# eBox_ACdetect.net
KiCad netlist of a schematic drawn in Altium Designer
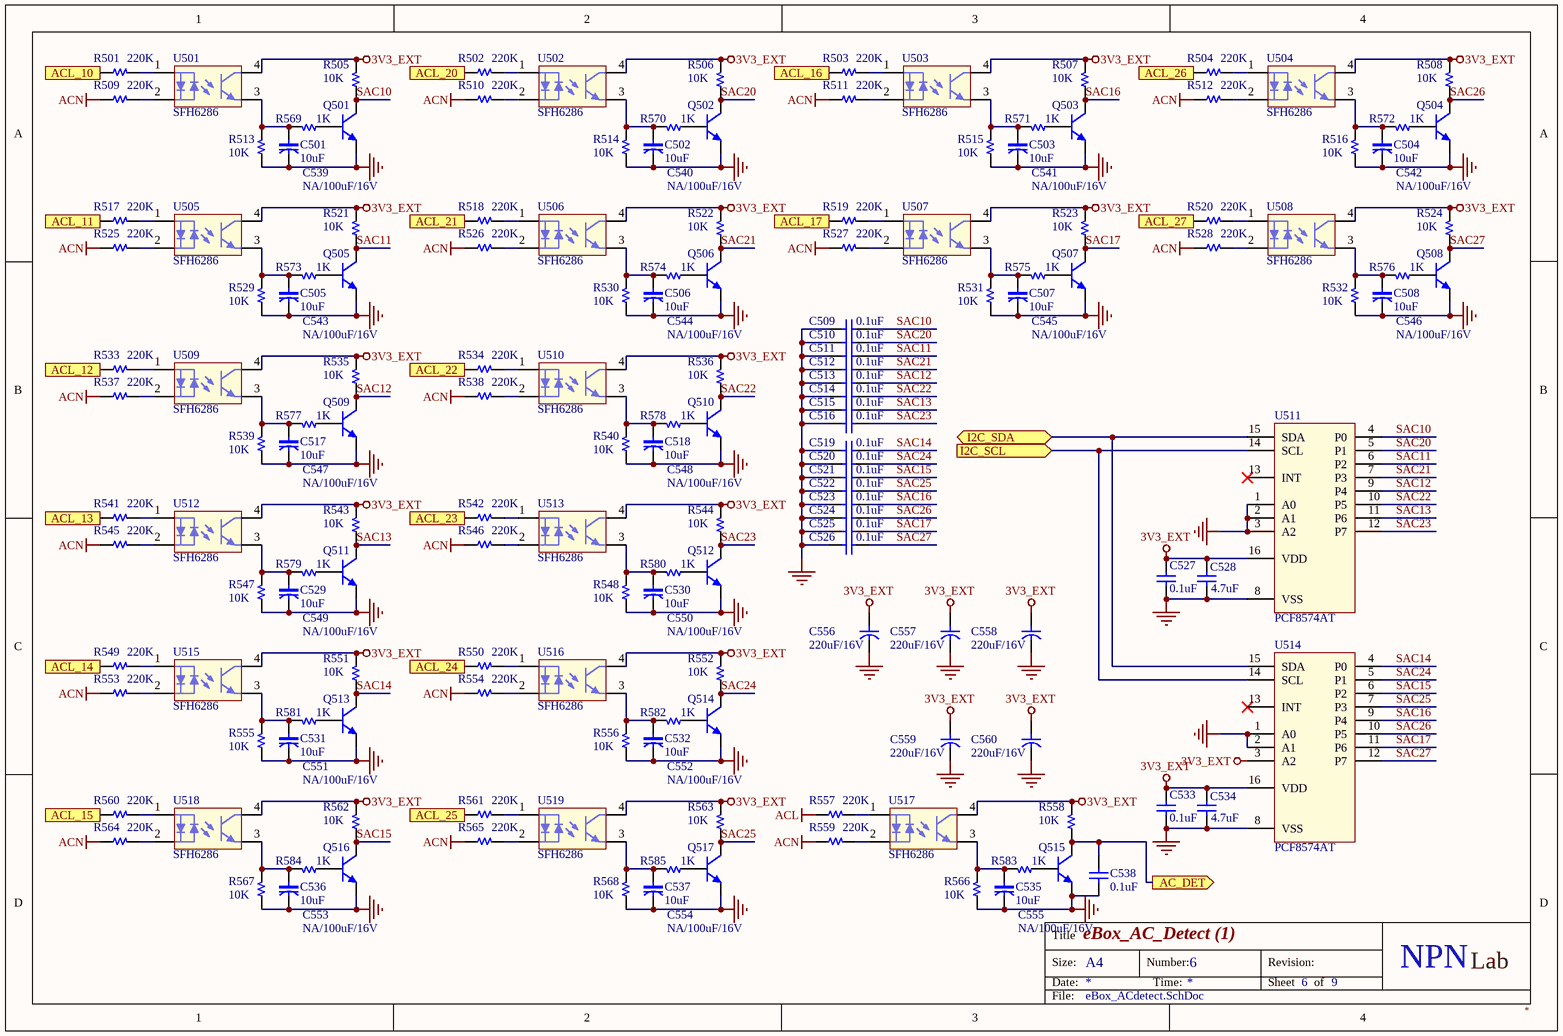
[diagram p0: eBox_ACdetect.SchDoc]

(export (version "E")
  (design (tool "Eeschema 10.0.6"))
  (components
    (comp (ref "C501")
      (value "10uF")
      (footprint "C 0805")
      (description "CAP CER 0.1UF 50V X7R 0805")
      (libsource (lib "chipfc_altium_libs") (part "Capacitor NP"))
    )
    (comp (ref "C502")
      (value "10uF")
      (footprint "C 0805")
      (description "CAP CER 0.1UF 50V X7R 0805")
      (libsource (lib "chipfc_altium_libs") (part "Capacitor NP"))
    )
    (comp (ref "C503")
      (value "10uF")
      (footprint "C 0805")
      (description "CAP CER 0.1UF 50V X7R 0805")
      (libsource (lib "chipfc_altium_libs") (part "Capacitor NP"))
    )
    (comp (ref "C504")
      (value "10uF")
      (footprint "C 0805")
      (description "CAP CER 0.1UF 50V X7R 0805")
      (libsource (lib "chipfc_altium_libs") (part "Capacitor NP"))
    )
    (comp (ref "C505")
      (value "10uF")
      (footprint "C 0805")
      (description "CAP CER 0.1UF 50V X7R 0805")
      (libsource (lib "chipfc_altium_libs") (part "Capacitor NP"))
    )
    (comp (ref "C506")
      (value "10uF")
      (footprint "C 0805")
      (description "CAP CER 0.1UF 50V X7R 0805")
      (libsource (lib "chipfc_altium_libs") (part "Capacitor NP"))
    )
    (comp (ref "C507")
      (value "10uF")
      (footprint "C 0805")
      (description "CAP CER 0.1UF 50V X7R 0805")
      (libsource (lib "chipfc_altium_libs") (part "Capacitor NP"))
    )
    (comp (ref "C508")
      (value "10uF")
      (footprint "C 0805")
      (description "CAP CER 0.1UF 50V X7R 0805")
      (libsource (lib "chipfc_altium_libs") (part "Capacitor NP"))
    )
    (comp (ref "C509")
      (value "0.1uF")
      (footprint "C 0805")
      (description "CAP CER 0.1UF 50V X7R 0805")
      (libsource (lib "chipfc_altium_libs") (part "Capacitor NP"))
    )
    (comp (ref "C510")
      (value "0.1uF")
      (footprint "C 0805")
      (description "CAP CER 0.1UF 50V X7R 0805")
      (libsource (lib "chipfc_altium_libs") (part "Capacitor NP"))
    )
    (comp (ref "C511")
      (value "0.1uF")
      (footprint "C 0805")
      (description "CAP CER 0.1UF 50V X7R 0805")
      (libsource (lib "chipfc_altium_libs") (part "Capacitor NP"))
    )
    (comp (ref "C512")
      (value "0.1uF")
      (footprint "C 0805")
      (description "CAP CER 0.1UF 50V X7R 0805")
      (libsource (lib "chipfc_altium_libs") (part "Capacitor NP"))
    )
    (comp (ref "C513")
      (value "0.1uF")
      (footprint "C 0805")
      (description "CAP CER 0.1UF 50V X7R 0805")
      (libsource (lib "chipfc_altium_libs") (part "Capacitor NP"))
    )
    (comp (ref "C514")
      (value "0.1uF")
      (footprint "C 0805")
      (description "CAP CER 0.1UF 50V X7R 0805")
      (libsource (lib "chipfc_altium_libs") (part "Capacitor NP"))
    )
    (comp (ref "C515")
      (value "0.1uF")
      (footprint "C 0805")
      (description "CAP CER 0.1UF 50V X7R 0805")
      (libsource (lib "chipfc_altium_libs") (part "Capacitor NP"))
    )
    (comp (ref "C516")
      (value "0.1uF")
      (footprint "C 0805")
      (description "CAP CER 0.1UF 50V X7R 0805")
      (libsource (lib "chipfc_altium_libs") (part "Capacitor NP"))
    )
    (comp (ref "C517")
      (value "10uF")
      (footprint "C 0805")
      (description "CAP CER 0.1UF 50V X7R 0805")
      (libsource (lib "chipfc_altium_libs") (part "Capacitor NP"))
    )
    (comp (ref "C518")
      (value "10uF")
      (footprint "C 0805")
      (description "CAP CER 0.1UF 50V X7R 0805")
      (libsource (lib "chipfc_altium_libs") (part "Capacitor NP"))
    )
    (comp (ref "C519")
      (value "0.1uF")
      (footprint "C 0805")
      (description "CAP CER 0.1UF 50V X7R 0805")
      (libsource (lib "chipfc_altium_libs") (part "Capacitor NP"))
    )
    (comp (ref "C520")
      (value "0.1uF")
      (footprint "C 0805")
      (description "CAP CER 0.1UF 50V X7R 0805")
      (libsource (lib "chipfc_altium_libs") (part "Capacitor NP"))
    )
    (comp (ref "C521")
      (value "0.1uF")
      (footprint "C 0805")
      (description "CAP CER 0.1UF 50V X7R 0805")
      (libsource (lib "chipfc_altium_libs") (part "Capacitor NP"))
    )
    (comp (ref "C522")
      (value "0.1uF")
      (footprint "C 0805")
      (description "CAP CER 0.1UF 50V X7R 0805")
      (libsource (lib "chipfc_altium_libs") (part "Capacitor NP"))
    )
    (comp (ref "C523")
      (value "0.1uF")
      (footprint "C 0805")
      (description "CAP CER 0.1UF 50V X7R 0805")
      (libsource (lib "chipfc_altium_libs") (part "Capacitor NP"))
    )
    (comp (ref "C524")
      (value "0.1uF")
      (footprint "C 0805")
      (description "CAP CER 0.1UF 50V X7R 0805")
      (libsource (lib "chipfc_altium_libs") (part "Capacitor NP"))
    )
    (comp (ref "C525")
      (value "0.1uF")
      (footprint "C 0805")
      (description "CAP CER 0.1UF 50V X7R 0805")
      (libsource (lib "chipfc_altium_libs") (part "Capacitor NP"))
    )
    (comp (ref "C526")
      (value "0.1uF")
      (footprint "C 0805")
      (description "CAP CER 0.1UF 50V X7R 0805")
      (libsource (lib "chipfc_altium_libs") (part "Capacitor NP"))
    )
    (comp (ref "C527")
      (value "0.1uF")
      (footprint "C 0603")
      (description "CAP CER 0.1UF 50V X7R 0603")
      (libsource (lib "chipfc_altium_libs") (part "Capacitor NP"))
    )
    (comp (ref "C528")
      (value "4.7uF")
      (footprint "C 0603")
      (description "CAP CER 4.7UF 50V X7R 0603")
      (libsource (lib "chipfc_altium_libs") (part "Capacitor NP"))
    )
    (comp (ref "C529")
      (value "10uF")
      (footprint "C 0805")
      (description "CAP CER 0.1UF 50V X7R 0805")
      (libsource (lib "chipfc_altium_libs") (part "Capacitor NP"))
    )
    (comp (ref "C530")
      (value "10uF")
      (footprint "C 0805")
      (description "CAP CER 0.1UF 50V X7R 0805")
      (libsource (lib "chipfc_altium_libs") (part "Capacitor NP"))
    )
    (comp (ref "C531")
      (value "10uF")
      (footprint "C 0805")
      (description "CAP CER 0.1UF 50V X7R 0805")
      (libsource (lib "chipfc_altium_libs") (part "Capacitor NP"))
    )
    (comp (ref "C532")
      (value "10uF")
      (footprint "C 0805")
      (description "CAP CER 0.1UF 50V X7R 0805")
      (libsource (lib "chipfc_altium_libs") (part "Capacitor NP"))
    )
    (comp (ref "C533")
      (value "0.1uF")
      (footprint "C 0603")
      (description "CAP CER 0.1UF 50V X7R 0603")
      (libsource (lib "chipfc_altium_libs") (part "Capacitor NP"))
    )
    (comp (ref "C534")
      (value "4.7uF")
      (footprint "C 0603")
      (description "CAP CER 4.7UF 50V X7R 0603")
      (libsource (lib "chipfc_altium_libs") (part "Capacitor NP"))
    )
    (comp (ref "C535")
      (value "10uF")
      (footprint "C 0805")
      (description "CAP CER 0.1UF 50V X7R 0805")
      (libsource (lib "chipfc_altium_libs") (part "Capacitor NP"))
    )
    (comp (ref "C536")
      (value "10uF")
      (footprint "C 0805")
      (description "CAP CER 0.1UF 50V X7R 0805")
      (libsource (lib "chipfc_altium_libs") (part "Capacitor NP"))
    )
    (comp (ref "C537")
      (value "10uF")
      (footprint "C 0805")
      (description "CAP CER 0.1UF 50V X7R 0805")
      (libsource (lib "chipfc_altium_libs") (part "Capacitor NP"))
    )
    (comp (ref "C538")
      (value "0.1uF")
      (footprint "C 0805")
      (description "CAP CER 0.1UF 50V X7R 0805")
      (libsource (lib "chipfc_altium_libs") (part "Capacitor NP"))
    )
    (comp (ref "C539")
      (value "NA/100uF/16V")
      (footprint "CYL/D.200/LS.75")
      (description "CAP ALUM 100UF 20% 16V RADIAL")
      (libsource (lib "chipfc_altium_libs") (part "Capacitor"))
    )
    (comp (ref "C540")
      (value "NA/100uF/16V")
      (footprint "CYL/D.200/LS.75")
      (description "CAP ALUM 100UF 20% 16V RADIAL")
      (libsource (lib "chipfc_altium_libs") (part "Capacitor"))
    )
    (comp (ref "C541")
      (value "NA/100uF/16V")
      (footprint "CYL/D.200/LS.75")
      (description "CAP ALUM 100UF 20% 16V RADIAL")
      (libsource (lib "chipfc_altium_libs") (part "Capacitor"))
    )
    (comp (ref "C542")
      (value "NA/100uF/16V")
      (footprint "CYL/D.200/LS.75")
      (description "CAP ALUM 100UF 20% 16V RADIAL")
      (libsource (lib "chipfc_altium_libs") (part "Capacitor"))
    )
    (comp (ref "C543")
      (value "NA/100uF/16V")
      (footprint "CYL/D.200/LS.75")
      (description "CAP ALUM 100UF 20% 16V RADIAL")
      (libsource (lib "chipfc_altium_libs") (part "Capacitor"))
    )
    (comp (ref "C544")
      (value "NA/100uF/16V")
      (footprint "CYL/D.200/LS.75")
      (description "CAP ALUM 100UF 20% 16V RADIAL")
      (libsource (lib "chipfc_altium_libs") (part "Capacitor"))
    )
    (comp (ref "C545")
      (value "NA/100uF/16V")
      (footprint "CYL/D.200/LS.75")
      (description "CAP ALUM 100UF 20% 16V RADIAL")
      (libsource (lib "chipfc_altium_libs") (part "Capacitor"))
    )
    (comp (ref "C546")
      (value "NA/100uF/16V")
      (footprint "CYL/D.200/LS.75")
      (description "CAP ALUM 100UF 20% 16V RADIAL")
      (libsource (lib "chipfc_altium_libs") (part "Capacitor"))
    )
    (comp (ref "C547")
      (value "NA/100uF/16V")
      (footprint "CYL/D.200/LS.75")
      (description "CAP ALUM 100UF 20% 16V RADIAL")
      (libsource (lib "chipfc_altium_libs") (part "Capacitor"))
    )
    (comp (ref "C548")
      (value "NA/100uF/16V")
      (footprint "CYL/D.200/LS.75")
      (description "CAP ALUM 100UF 20% 16V RADIAL")
      (libsource (lib "chipfc_altium_libs") (part "Capacitor"))
    )
    (comp (ref "C549")
      (value "NA/100uF/16V")
      (footprint "CYL/D.200/LS.75")
      (description "CAP ALUM 100UF 20% 16V RADIAL")
      (libsource (lib "chipfc_altium_libs") (part "Capacitor"))
    )
    (comp (ref "C550")
      (value "NA/100uF/16V")
      (footprint "CYL/D.200/LS.75")
      (description "CAP ALUM 100UF 20% 16V RADIAL")
      (libsource (lib "chipfc_altium_libs") (part "Capacitor"))
    )
    (comp (ref "C551")
      (value "NA/100uF/16V")
      (footprint "CYL/D.200/LS.75")
      (description "CAP ALUM 100UF 20% 16V RADIAL")
      (libsource (lib "chipfc_altium_libs") (part "Capacitor"))
    )
    (comp (ref "C552")
      (value "NA/100uF/16V")
      (footprint "CYL/D.200/LS.75")
      (description "CAP ALUM 100UF 20% 16V RADIAL")
      (libsource (lib "chipfc_altium_libs") (part "Capacitor"))
    )
    (comp (ref "C553")
      (value "NA/100uF/16V")
      (footprint "CYL/D.200/LS.75")
      (description "CAP ALUM 100UF 20% 16V RADIAL")
      (libsource (lib "chipfc_altium_libs") (part "Capacitor"))
    )
    (comp (ref "C554")
      (value "NA/100uF/16V")
      (footprint "CYL/D.200/LS.75")
      (description "CAP ALUM 100UF 20% 16V RADIAL")
      (libsource (lib "chipfc_altium_libs") (part "Capacitor"))
    )
    (comp (ref "C555")
      (value "NA/100uF/16V")
      (footprint "CYL/D.200/LS.75")
      (description "CAP ALUM 100UF 20% 16V RADIAL")
      (libsource (lib "chipfc_altium_libs") (part "Capacitor"))
    )
    (comp (ref "C556")
      (value "220uF/16V")
      (footprint "CYL/D.250/LS.100")
      (description "CAP ALUM 220UF 20% 16V RADIAL")
      (libsource (lib "") (part "Capacitor_1"))
    )
    (comp (ref "C557")
      (value "220uF/16V")
      (footprint "CYL/D.250/LS.100")
      (description "CAP ALUM 220UF 20% 16V RADIAL")
      (libsource (lib "") (part "Capacitor_1"))
    )
    (comp (ref "C558")
      (value "220uF/16V")
      (footprint "CYL/D.250/LS.100")
      (description "CAP ALUM 220UF 20% 16V RADIAL")
      (libsource (lib "") (part "Capacitor_1"))
    )
    (comp (ref "C559")
      (value "220uF/16V")
      (footprint "CYL/D.250/LS.100")
      (description "CAP ALUM 220UF 20% 16V RADIAL")
      (libsource (lib "") (part "Capacitor_1"))
    )
    (comp (ref "C560")
      (value "220uF/16V")
      (footprint "CYL/D.250/LS.100")
      (description "CAP ALUM 220UF 20% 16V RADIAL")
      (libsource (lib "") (part "Capacitor_1"))
    )
    (comp (ref "Q501")
      (value "MMBT3904LT1G")
      (footprint "SOT-23")
      (description "TRANS NPN 40V 0.2A SOT23")
      (libsource (lib "chipfc_altium_libs") (part "Transistor NPN"))
    )
    (comp (ref "Q502")
      (value "MMBT3904LT1G")
      (footprint "SOT-23")
      (description "TRANS NPN 40V 0.2A SOT23")
      (libsource (lib "chipfc_altium_libs") (part "Transistor NPN"))
    )
    (comp (ref "Q503")
      (value "MMBT3904LT1G")
      (footprint "SOT-23")
      (description "TRANS NPN 40V 0.2A SOT23")
      (libsource (lib "chipfc_altium_libs") (part "Transistor NPN"))
    )
    (comp (ref "Q504")
      (value "MMBT3904LT1G")
      (footprint "SOT-23")
      (description "TRANS NPN 40V 0.2A SOT23")
      (libsource (lib "chipfc_altium_libs") (part "Transistor NPN"))
    )
    (comp (ref "Q505")
      (value "MMBT3904LT1G")
      (footprint "SOT-23")
      (description "TRANS NPN 40V 0.2A SOT23")
      (libsource (lib "chipfc_altium_libs") (part "Transistor NPN"))
    )
    (comp (ref "Q506")
      (value "MMBT3904LT1G")
      (footprint "SOT-23")
      (description "TRANS NPN 40V 0.2A SOT23")
      (libsource (lib "chipfc_altium_libs") (part "Transistor NPN"))
    )
    (comp (ref "Q507")
      (value "MMBT3904LT1G")
      (footprint "SOT-23")
      (description "TRANS NPN 40V 0.2A SOT23")
      (libsource (lib "chipfc_altium_libs") (part "Transistor NPN"))
    )
    (comp (ref "Q508")
      (value "MMBT3904LT1G")
      (footprint "SOT-23")
      (description "TRANS NPN 40V 0.2A SOT23")
      (libsource (lib "chipfc_altium_libs") (part "Transistor NPN"))
    )
    (comp (ref "Q509")
      (value "MMBT3904LT1G")
      (footprint "SOT-23")
      (description "TRANS NPN 40V 0.2A SOT23")
      (libsource (lib "chipfc_altium_libs") (part "Transistor NPN"))
    )
    (comp (ref "Q510")
      (value "MMBT3904LT1G")
      (footprint "SOT-23")
      (description "TRANS NPN 40V 0.2A SOT23")
      (libsource (lib "chipfc_altium_libs") (part "Transistor NPN"))
    )
    (comp (ref "Q511")
      (value "MMBT3904LT1G")
      (footprint "SOT-23")
      (description "TRANS NPN 40V 0.2A SOT23")
      (libsource (lib "chipfc_altium_libs") (part "Transistor NPN"))
    )
    (comp (ref "Q512")
      (value "MMBT3904LT1G")
      (footprint "SOT-23")
      (description "TRANS NPN 40V 0.2A SOT23")
      (libsource (lib "chipfc_altium_libs") (part "Transistor NPN"))
    )
    (comp (ref "Q513")
      (value "MMBT3904LT1G")
      (footprint "SOT-23")
      (description "TRANS NPN 40V 0.2A SOT23")
      (libsource (lib "chipfc_altium_libs") (part "Transistor NPN"))
    )
    (comp (ref "Q514")
      (value "MMBT3904LT1G")
      (footprint "SOT-23")
      (description "TRANS NPN 40V 0.2A SOT23")
      (libsource (lib "chipfc_altium_libs") (part "Transistor NPN"))
    )
    (comp (ref "Q515")
      (value "MMBT3904LT1G")
      (footprint "SOT-23")
      (description "TRANS NPN 40V 0.2A SOT23")
      (libsource (lib "chipfc_altium_libs") (part "Transistor NPN"))
    )
    (comp (ref "Q516")
      (value "MMBT3904LT1G")
      (footprint "SOT-23")
      (description "TRANS NPN 40V 0.2A SOT23")
      (libsource (lib "chipfc_altium_libs") (part "Transistor NPN"))
    )
    (comp (ref "Q517")
      (value "MMBT3904LT1G")
      (footprint "SOT-23")
      (description "TRANS NPN 40V 0.2A SOT23")
      (libsource (lib "chipfc_altium_libs") (part "Transistor NPN"))
    )
    (comp (ref "R501")
      (value "220K")
      (footprint "R 0805")
      (description "RES SMD 220K OHM 1% 1/8W 0805")
      (libsource (lib "chipfc_altium_libs") (part "Resistor"))
    )
    (comp (ref "R502")
      (value "220K")
      (footprint "R 0805")
      (description "RES SMD 220K OHM 1% 1/8W 0805")
      (libsource (lib "chipfc_altium_libs") (part "Resistor"))
    )
    (comp (ref "R503")
      (value "220K")
      (footprint "R 0805")
      (description "RES SMD 220K OHM 1% 1/8W 0805")
      (libsource (lib "chipfc_altium_libs") (part "Resistor"))
    )
    (comp (ref "R504")
      (value "220K")
      (footprint "R 0805")
      (description "RES SMD 220K OHM 1% 1/8W 0805")
      (libsource (lib "chipfc_altium_libs") (part "Resistor"))
    )
    (comp (ref "R505")
      (value "10K")
      (footprint "R 0805")
      (description "RES SMD 10K OHM 1% 1/8W 0805")
      (libsource (lib "chipfc_altium_libs") (part "Resistor"))
    )
    (comp (ref "R506")
      (value "10K")
      (footprint "R 0805")
      (description "RES SMD 10K OHM 1% 1/8W 0805")
      (libsource (lib "chipfc_altium_libs") (part "Resistor"))
    )
    (comp (ref "R507")
      (value "10K")
      (footprint "R 0805")
      (description "RES SMD 10K OHM 1% 1/8W 0805")
      (libsource (lib "chipfc_altium_libs") (part "Resistor"))
    )
    (comp (ref "R508")
      (value "10K")
      (footprint "R 0805")
      (description "RES SMD 10K OHM 1% 1/8W 0805")
      (libsource (lib "chipfc_altium_libs") (part "Resistor"))
    )
    (comp (ref "R509")
      (value "220K")
      (footprint "R 0805")
      (description "RES SMD 220K OHM 1% 1/8W 0805")
      (libsource (lib "chipfc_altium_libs") (part "Resistor"))
    )
    (comp (ref "R510")
      (value "220K")
      (footprint "R 0805")
      (description "RES SMD 220K OHM 1% 1/8W 0805")
      (libsource (lib "chipfc_altium_libs") (part "Resistor"))
    )
    (comp (ref "R511")
      (value "220K")
      (footprint "R 0805")
      (description "RES SMD 220K OHM 1% 1/8W 0805")
      (libsource (lib "chipfc_altium_libs") (part "Resistor"))
    )
    (comp (ref "R512")
      (value "220K")
      (footprint "R 0805")
      (description "RES SMD 220K OHM 1% 1/8W 0805")
      (libsource (lib "chipfc_altium_libs") (part "Resistor"))
    )
    (comp (ref "R513")
      (value "10K")
      (footprint "R 0805")
      (description "RES SMD 10K OHM 1% 1/8W 0805")
      (libsource (lib "chipfc_altium_libs") (part "Resistor"))
    )
    (comp (ref "R514")
      (value "10K")
      (footprint "R 0805")
      (description "RES SMD 10K OHM 1% 1/8W 0805")
      (libsource (lib "chipfc_altium_libs") (part "Resistor"))
    )
    (comp (ref "R515")
      (value "10K")
      (footprint "R 0805")
      (description "RES SMD 10K OHM 1% 1/8W 0805")
      (libsource (lib "chipfc_altium_libs") (part "Resistor"))
    )
    (comp (ref "R516")
      (value "10K")
      (footprint "R 0805")
      (description "RES SMD 10K OHM 1% 1/8W 0805")
      (libsource (lib "chipfc_altium_libs") (part "Resistor"))
    )
    (comp (ref "R517")
      (value "220K")
      (footprint "R 0805")
      (description "RES SMD 220K OHM 1% 1/8W 0805")
      (libsource (lib "chipfc_altium_libs") (part "Resistor"))
    )
    (comp (ref "R518")
      (value "220K")
      (footprint "R 0805")
      (description "RES SMD 220K OHM 1% 1/8W 0805")
      (libsource (lib "chipfc_altium_libs") (part "Resistor"))
    )
    (comp (ref "R519")
      (value "220K")
      (footprint "R 0805")
      (description "RES SMD 220K OHM 1% 1/8W 0805")
      (libsource (lib "chipfc_altium_libs") (part "Resistor"))
    )
    (comp (ref "R520")
      (value "220K")
      (footprint "R 0805")
      (description "RES SMD 220K OHM 1% 1/8W 0805")
      (libsource (lib "chipfc_altium_libs") (part "Resistor"))
    )
    (comp (ref "R521")
      (value "10K")
      (footprint "R 0805")
      (description "RES SMD 10K OHM 1% 1/8W 0805")
      (libsource (lib "chipfc_altium_libs") (part "Resistor"))
    )
    (comp (ref "R522")
      (value "10K")
      (footprint "R 0805")
      (description "RES SMD 10K OHM 1% 1/8W 0805")
      (libsource (lib "chipfc_altium_libs") (part "Resistor"))
    )
    (comp (ref "R523")
      (value "10K")
      (footprint "R 0805")
      (description "RES SMD 10K OHM 1% 1/8W 0805")
      (libsource (lib "chipfc_altium_libs") (part "Resistor"))
    )
    (comp (ref "R524")
      (value "10K")
      (footprint "R 0805")
      (description "RES SMD 10K OHM 1% 1/8W 0805")
      (libsource (lib "chipfc_altium_libs") (part "Resistor"))
    )
    (comp (ref "R525")
      (value "220K")
      (footprint "R 0805")
      (description "RES SMD 220K OHM 1% 1/8W 0805")
      (libsource (lib "chipfc_altium_libs") (part "Resistor"))
    )
    (comp (ref "R526")
      (value "220K")
      (footprint "R 0805")
      (description "RES SMD 220K OHM 1% 1/8W 0805")
      (libsource (lib "chipfc_altium_libs") (part "Resistor"))
    )
    (comp (ref "R527")
      (value "220K")
      (footprint "R 0805")
      (description "RES SMD 220K OHM 1% 1/8W 0805")
      (libsource (lib "chipfc_altium_libs") (part "Resistor"))
    )
    (comp (ref "R528")
      (value "220K")
      (footprint "R 0805")
      (description "RES SMD 220K OHM 1% 1/8W 0805")
      (libsource (lib "chipfc_altium_libs") (part "Resistor"))
    )
    (comp (ref "R529")
      (value "10K")
      (footprint "R 0805")
      (description "RES SMD 10K OHM 1% 1/8W 0805")
      (libsource (lib "chipfc_altium_libs") (part "Resistor"))
    )
    (comp (ref "R530")
      (value "10K")
      (footprint "R 0805")
      (description "RES SMD 10K OHM 1% 1/8W 0805")
      (libsource (lib "chipfc_altium_libs") (part "Resistor"))
    )
    (comp (ref "R531")
      (value "10K")
      (footprint "R 0805")
      (description "RES SMD 10K OHM 1% 1/8W 0805")
      (libsource (lib "chipfc_altium_libs") (part "Resistor"))
    )
    (comp (ref "R532")
      (value "10K")
      (footprint "R 0805")
      (description "RES SMD 10K OHM 1% 1/8W 0805")
      (libsource (lib "chipfc_altium_libs") (part "Resistor"))
    )
    (comp (ref "R533")
      (value "220K")
      (footprint "R 0805")
      (description "RES SMD 220K OHM 1% 1/8W 0805")
      (libsource (lib "chipfc_altium_libs") (part "Resistor"))
    )
    (comp (ref "R534")
      (value "220K")
      (footprint "R 0805")
      (description "RES SMD 220K OHM 1% 1/8W 0805")
      (libsource (lib "chipfc_altium_libs") (part "Resistor"))
    )
    (comp (ref "R535")
      (value "10K")
      (footprint "R 0805")
      (description "RES SMD 10K OHM 1% 1/8W 0805")
      (libsource (lib "chipfc_altium_libs") (part "Resistor"))
    )
    (comp (ref "R536")
      (value "10K")
      (footprint "R 0805")
      (description "RES SMD 10K OHM 1% 1/8W 0805")
      (libsource (lib "chipfc_altium_libs") (part "Resistor"))
    )
    (comp (ref "R537")
      (value "220K")
      (footprint "R 0805")
      (description "RES SMD 220K OHM 1% 1/8W 0805")
      (libsource (lib "chipfc_altium_libs") (part "Resistor"))
    )
    (comp (ref "R538")
      (value "220K")
      (footprint "R 0805")
      (description "RES SMD 220K OHM 1% 1/8W 0805")
      (libsource (lib "chipfc_altium_libs") (part "Resistor"))
    )
    (comp (ref "R539")
      (value "10K")
      (footprint "R 0805")
      (description "RES SMD 10K OHM 1% 1/8W 0805")
      (libsource (lib "chipfc_altium_libs") (part "Resistor"))
    )
    (comp (ref "R540")
      (value "10K")
      (footprint "R 0805")
      (description "RES SMD 10K OHM 1% 1/8W 0805")
      (libsource (lib "chipfc_altium_libs") (part "Resistor"))
    )
    (comp (ref "R541")
      (value "220K")
      (footprint "R 0805")
      (description "RES SMD 220K OHM 1% 1/8W 0805")
      (libsource (lib "chipfc_altium_libs") (part "Resistor"))
    )
    (comp (ref "R542")
      (value "220K")
      (footprint "R 0805")
      (description "RES SMD 220K OHM 1% 1/8W 0805")
      (libsource (lib "chipfc_altium_libs") (part "Resistor"))
    )
    (comp (ref "R543")
      (value "10K")
      (footprint "R 0805")
      (description "RES SMD 10K OHM 1% 1/8W 0805")
      (libsource (lib "chipfc_altium_libs") (part "Resistor"))
    )
    (comp (ref "R544")
      (value "10K")
      (footprint "R 0805")
      (description "RES SMD 10K OHM 1% 1/8W 0805")
      (libsource (lib "chipfc_altium_libs") (part "Resistor"))
    )
    (comp (ref "R545")
      (value "220K")
      (footprint "R 0805")
      (description "RES SMD 220K OHM 1% 1/8W 0805")
      (libsource (lib "chipfc_altium_libs") (part "Resistor"))
    )
    (comp (ref "R546")
      (value "220K")
      (footprint "R 0805")
      (description "RES SMD 220K OHM 1% 1/8W 0805")
      (libsource (lib "chipfc_altium_libs") (part "Resistor"))
    )
    (comp (ref "R547")
      (value "10K")
      (footprint "R 0805")
      (description "RES SMD 10K OHM 1% 1/8W 0805")
      (libsource (lib "chipfc_altium_libs") (part "Resistor"))
    )
    (comp (ref "R548")
      (value "10K")
      (footprint "R 0805")
      (description "RES SMD 10K OHM 1% 1/8W 0805")
      (libsource (lib "chipfc_altium_libs") (part "Resistor"))
    )
    (comp (ref "R549")
      (value "220K")
      (footprint "R 0805")
      (description "RES SMD 220K OHM 1% 1/8W 0805")
      (libsource (lib "chipfc_altium_libs") (part "Resistor"))
    )
    (comp (ref "R550")
      (value "220K")
      (footprint "R 0805")
      (description "RES SMD 220K OHM 1% 1/8W 0805")
      (libsource (lib "chipfc_altium_libs") (part "Resistor"))
    )
    (comp (ref "R551")
      (value "10K")
      (footprint "R 0805")
      (description "RES SMD 10K OHM 1% 1/8W 0805")
      (libsource (lib "chipfc_altium_libs") (part "Resistor"))
    )
    (comp (ref "R552")
      (value "10K")
      (footprint "R 0805")
      (description "RES SMD 10K OHM 1% 1/8W 0805")
      (libsource (lib "chipfc_altium_libs") (part "Resistor"))
    )
    (comp (ref "R553")
      (value "220K")
      (footprint "R 0805")
      (description "RES SMD 220K OHM 1% 1/8W 0805")
      (libsource (lib "chipfc_altium_libs") (part "Resistor"))
    )
    (comp (ref "R554")
      (value "220K")
      (footprint "R 0805")
      (description "RES SMD 220K OHM 1% 1/8W 0805")
      (libsource (lib "chipfc_altium_libs") (part "Resistor"))
    )
    (comp (ref "R555")
      (value "10K")
      (footprint "R 0805")
      (description "RES SMD 10K OHM 1% 1/8W 0805")
      (libsource (lib "chipfc_altium_libs") (part "Resistor"))
    )
    (comp (ref "R556")
      (value "10K")
      (footprint "R 0805")
      (description "RES SMD 10K OHM 1% 1/8W 0805")
      (libsource (lib "chipfc_altium_libs") (part "Resistor"))
    )
    (comp (ref "R557")
      (value "220K")
      (footprint "R 0805")
      (description "RES SMD 220K OHM 1% 1/8W 0805")
      (libsource (lib "chipfc_altium_libs") (part "Resistor"))
    )
    (comp (ref "R558")
      (value "10K")
      (footprint "R 0805")
      (description "RES SMD 10K OHM 1% 1/8W 0805")
      (libsource (lib "chipfc_altium_libs") (part "Resistor"))
    )
    (comp (ref "R559")
      (value "220K")
      (footprint "R 0805")
      (description "RES SMD 220K OHM 1% 1/8W 0805")
      (libsource (lib "chipfc_altium_libs") (part "Resistor"))
    )
    (comp (ref "R560")
      (value "220K")
      (footprint "R 0805")
      (description "RES SMD 220K OHM 1% 1/8W 0805")
      (libsource (lib "chipfc_altium_libs") (part "Resistor"))
    )
    (comp (ref "R561")
      (value "220K")
      (footprint "R 0805")
      (description "RES SMD 220K OHM 1% 1/8W 0805")
      (libsource (lib "chipfc_altium_libs") (part "Resistor"))
    )
    (comp (ref "R562")
      (value "10K")
      (footprint "R 0805")
      (description "RES SMD 10K OHM 1% 1/8W 0805")
      (libsource (lib "chipfc_altium_libs") (part "Resistor"))
    )
    (comp (ref "R563")
      (value "10K")
      (footprint "R 0805")
      (description "RES SMD 10K OHM 1% 1/8W 0805")
      (libsource (lib "chipfc_altium_libs") (part "Resistor"))
    )
    (comp (ref "R564")
      (value "220K")
      (footprint "R 0805")
      (description "RES SMD 220K OHM 1% 1/8W 0805")
      (libsource (lib "chipfc_altium_libs") (part "Resistor"))
    )
    (comp (ref "R565")
      (value "220K")
      (footprint "R 0805")
      (description "RES SMD 220K OHM 1% 1/8W 0805")
      (libsource (lib "chipfc_altium_libs") (part "Resistor"))
    )
    (comp (ref "R566")
      (value "10K")
      (footprint "R 0805")
      (description "RES SMD 10K OHM 1% 1/8W 0805")
      (libsource (lib "chipfc_altium_libs") (part "Resistor"))
    )
    (comp (ref "R567")
      (value "10K")
      (footprint "R 0805")
      (description "RES SMD 10K OHM 1% 1/8W 0805")
      (libsource (lib "chipfc_altium_libs") (part "Resistor"))
    )
    (comp (ref "R568")
      (value "10K")
      (footprint "R 0805")
      (description "RES SMD 10K OHM 1% 1/8W 0805")
      (libsource (lib "chipfc_altium_libs") (part "Resistor"))
    )
    (comp (ref "R569")
      (value "1K")
      (footprint "R 0805")
      (description "RES SMD 1K OHM 5% 1/8W 0805")
      (libsource (lib "chipfc_altium_libs") (part "Resistor"))
    )
    (comp (ref "R570")
      (value "1K")
      (footprint "R 0805")
      (description "RES SMD 1K OHM 5% 1/8W 0805")
      (libsource (lib "chipfc_altium_libs") (part "Resistor"))
    )
    (comp (ref "R571")
      (value "1K")
      (footprint "R 0805")
      (description "RES SMD 1K OHM 5% 1/8W 0805")
      (libsource (lib "chipfc_altium_libs") (part "Resistor"))
    )
    (comp (ref "R572")
      (value "1K")
      (footprint "R 0805")
      (description "RES SMD 1K OHM 5% 1/8W 0805")
      (libsource (lib "chipfc_altium_libs") (part "Resistor"))
    )
    (comp (ref "R573")
      (value "1K")
      (footprint "R 0805")
      (description "RES SMD 1K OHM 5% 1/8W 0805")
      (libsource (lib "chipfc_altium_libs") (part "Resistor"))
    )
    (comp (ref "R574")
      (value "1K")
      (footprint "R 0805")
      (description "RES SMD 1K OHM 5% 1/8W 0805")
      (libsource (lib "chipfc_altium_libs") (part "Resistor"))
    )
    (comp (ref "R575")
      (value "1K")
      (footprint "R 0805")
      (description "RES SMD 1K OHM 5% 1/8W 0805")
      (libsource (lib "chipfc_altium_libs") (part "Resistor"))
    )
    (comp (ref "R576")
      (value "1K")
      (footprint "R 0805")
      (description "RES SMD 1K OHM 5% 1/8W 0805")
      (libsource (lib "chipfc_altium_libs") (part "Resistor"))
    )
    (comp (ref "R577")
      (value "1K")
      (footprint "R 0805")
      (description "RES SMD 1K OHM 5% 1/8W 0805")
      (libsource (lib "chipfc_altium_libs") (part "Resistor"))
    )
    (comp (ref "R578")
      (value "1K")
      (footprint "R 0805")
      (description "RES SMD 1K OHM 5% 1/8W 0805")
      (libsource (lib "chipfc_altium_libs") (part "Resistor"))
    )
    (comp (ref "R579")
      (value "1K")
      (footprint "R 0805")
      (description "RES SMD 1K OHM 5% 1/8W 0805")
      (libsource (lib "chipfc_altium_libs") (part "Resistor"))
    )
    (comp (ref "R580")
      (value "1K")
      (footprint "R 0805")
      (description "RES SMD 1K OHM 5% 1/8W 0805")
      (libsource (lib "chipfc_altium_libs") (part "Resistor"))
    )
    (comp (ref "R581")
      (value "1K")
      (footprint "R 0805")
      (description "RES SMD 1K OHM 5% 1/8W 0805")
      (libsource (lib "chipfc_altium_libs") (part "Resistor"))
    )
    (comp (ref "R582")
      (value "1K")
      (footprint "R 0805")
      (description "RES SMD 1K OHM 5% 1/8W 0805")
      (libsource (lib "chipfc_altium_libs") (part "Resistor"))
    )
    (comp (ref "R583")
      (value "1K")
      (footprint "R 0805")
      (description "RES SMD 1K OHM 5% 1/8W 0805")
      (libsource (lib "chipfc_altium_libs") (part "Resistor"))
    )
    (comp (ref "R584")
      (value "1K")
      (footprint "R 0805")
      (description "RES SMD 1K OHM 5% 1/8W 0805")
      (libsource (lib "chipfc_altium_libs") (part "Resistor"))
    )
    (comp (ref "R585")
      (value "1K")
      (footprint "R 0805")
      (description "RES SMD 1K OHM 5% 1/8W 0805")
      (libsource (lib "chipfc_altium_libs") (part "Resistor"))
    )
    (comp (ref "U501")
      (value "SFH6286")
      (footprint "SOP4 - SFH6286")
      (libsource (lib "chipfc_altium_libs") (part "SFH6286"))
    )
    (comp (ref "U502")
      (value "SFH6286")
      (footprint "SOP4 - SFH6286")
      (libsource (lib "chipfc_altium_libs") (part "SFH6286"))
    )
    (comp (ref "U503")
      (value "SFH6286")
      (footprint "SOP4 - SFH6286")
      (libsource (lib "chipfc_altium_libs") (part "SFH6286"))
    )
    (comp (ref "U504")
      (value "SFH6286")
      (footprint "SOP4 - SFH6286")
      (libsource (lib "chipfc_altium_libs") (part "SFH6286"))
    )
    (comp (ref "U505")
      (value "SFH6286")
      (footprint "SOP4 - SFH6286")
      (libsource (lib "chipfc_altium_libs") (part "SFH6286"))
    )
    (comp (ref "U506")
      (value "SFH6286")
      (footprint "SOP4 - SFH6286")
      (libsource (lib "chipfc_altium_libs") (part "SFH6286"))
    )
    (comp (ref "U507")
      (value "SFH6286")
      (footprint "SOP4 - SFH6286")
      (libsource (lib "chipfc_altium_libs") (part "SFH6286"))
    )
    (comp (ref "U508")
      (value "SFH6286")
      (footprint "SOP4 - SFH6286")
      (libsource (lib "chipfc_altium_libs") (part "SFH6286"))
    )
    (comp (ref "U509")
      (value "SFH6286")
      (footprint "SOP4 - SFH6286")
      (libsource (lib "chipfc_altium_libs") (part "SFH6286"))
    )
    (comp (ref "U510")
      (value "SFH6286")
      (footprint "SOP4 - SFH6286")
      (libsource (lib "chipfc_altium_libs") (part "SFH6286"))
    )
    (comp (ref "U511")
      (value "PCF8574AT")
      (footprint "SO16/PCF8574AT")
      (description "Remote 8-bit I/O expander for I2C-bus with interrupt")
      (fields (field (name "PART NO") "PCF8574AT/3"))
      (libsource (lib "chipfc_altium_libs") (part "PCF8574AT"))
    )
    (comp (ref "U512")
      (value "SFH6286")
      (footprint "SOP4 - SFH6286")
      (libsource (lib "chipfc_altium_libs") (part "SFH6286"))
    )
    (comp (ref "U513")
      (value "SFH6286")
      (footprint "SOP4 - SFH6286")
      (libsource (lib "chipfc_altium_libs") (part "SFH6286"))
    )
    (comp (ref "U514")
      (value "PCF8574AT")
      (footprint "SO16/PCF8574AT")
      (description "Remote 8-bit I/O expander for I2C-bus with interrupt")
      (fields (field (name "PART NO") "PCF8574AT/3"))
      (libsource (lib "chipfc_altium_libs") (part "PCF8574AT"))
    )
    (comp (ref "U515")
      (value "SFH6286")
      (footprint "SOP4 - SFH6286")
      (libsource (lib "chipfc_altium_libs") (part "SFH6286"))
    )
    (comp (ref "U516")
      (value "SFH6286")
      (footprint "SOP4 - SFH6286")
      (libsource (lib "chipfc_altium_libs") (part "SFH6286"))
    )
    (comp (ref "U517")
      (value "SFH6286")
      (footprint "SOP4 - SFH6286")
      (libsource (lib "chipfc_altium_libs") (part "SFH6286"))
    )
    (comp (ref "U518")
      (value "SFH6286")
      (footprint "SOP4 - SFH6286")
      (libsource (lib "chipfc_altium_libs") (part "SFH6286"))
    )
    (comp (ref "U519")
      (value "SFH6286")
      (footprint "SOP4 - SFH6286")
      (libsource (lib "chipfc_altium_libs") (part "SFH6286"))
    )
  )
  (nets
    (net (code "1") (name "/ACL_10") (class "Default")
      (node (ref "R501") (pin "1") (pinfunction "1_1") (pintype "passive"))
    )
    (net (code "2") (name "/ACL_11") (class "Default")
      (node (ref "R517") (pin "1") (pinfunction "1_1") (pintype "passive"))
    )
    (net (code "3") (name "/ACL_12") (class "Default")
      (node (ref "R533") (pin "1") (pinfunction "1_1") (pintype "passive"))
    )
    (net (code "4") (name "/ACL_13") (class "Default")
      (node (ref "R541") (pin "1") (pinfunction "1_1") (pintype "passive"))
    )
    (net (code "5") (name "/ACL_14") (class "Default")
      (node (ref "R549") (pin "1") (pinfunction "1_1") (pintype "passive"))
    )
    (net (code "6") (name "/ACL_15") (class "Default")
      (node (ref "R560") (pin "1") (pinfunction "1_1") (pintype "passive"))
    )
    (net (code "7") (name "/ACL_16") (class "Default")
      (node (ref "R503") (pin "1") (pinfunction "1_1") (pintype "passive"))
    )
    (net (code "8") (name "/ACL_17") (class "Default")
      (node (ref "R519") (pin "1") (pinfunction "1_1") (pintype "passive"))
    )
    (net (code "9") (name "/ACL_20") (class "Default")
      (node (ref "R502") (pin "1") (pinfunction "1_1") (pintype "passive"))
    )
    (net (code "10") (name "/ACL_21") (class "Default")
      (node (ref "R518") (pin "1") (pinfunction "1_1") (pintype "passive"))
    )
    (net (code "11") (name "/ACL_22") (class "Default")
      (node (ref "R534") (pin "1") (pinfunction "1_1") (pintype "passive"))
    )
    (net (code "12") (name "/ACL_23") (class "Default")
      (node (ref "R542") (pin "1") (pinfunction "1_1") (pintype "passive"))
    )
    (net (code "13") (name "/ACL_24") (class "Default")
      (node (ref "R550") (pin "1") (pinfunction "1_1") (pintype "passive"))
    )
    (net (code "14") (name "/ACL_25") (class "Default")
      (node (ref "R561") (pin "1") (pinfunction "1_1") (pintype "passive"))
    )
    (net (code "15") (name "/ACL_26") (class "Default")
      (node (ref "R504") (pin "1") (pinfunction "1_1") (pintype "passive"))
    )
    (net (code "16") (name "/ACL_27") (class "Default")
      (node (ref "R520") (pin "1") (pinfunction "1_1") (pintype "passive"))
    )
    (net (code "17") (name "/AC_DET") (class "Default")
      (node (ref "C538") (pin "2") (pinfunction "2_2") (pintype "passive"))
      (node (ref "Q515") (pin "3") (pinfunction "C_3") (pintype "passive"))
      (node (ref "R558") (pin "1") (pinfunction "1_1") (pintype "passive"))
    )
    (net (code "18") (name "/I2C_SCL") (class "Default")
      (node (ref "U511") (pin "14") (pinfunction "SCL_14") (pintype "passive"))
      (node (ref "U514") (pin "14") (pinfunction "SCL_14") (pintype "passive"))
    )
    (net (code "19") (name "/I2C_SDA") (class "Default")
      (node (ref "U511") (pin "15") (pinfunction "SDA_15") (pintype "passive"))
      (node (ref "U514") (pin "15") (pinfunction "SDA_15") (pintype "passive"))
    )
    (net (code "20") (name "/SAC10") (class "Default")
      (node (ref "C509") (pin "2") (pinfunction "2_2") (pintype "passive"))
      (node (ref "Q501") (pin "3") (pinfunction "C_3") (pintype "passive"))
      (node (ref "R505") (pin "1") (pinfunction "1_1") (pintype "passive"))
      (node (ref "U511") (pin "4") (pinfunction "P0_4") (pintype "passive"))
    )
    (net (code "21") (name "/SAC11") (class "Default")
      (node (ref "C511") (pin "2") (pinfunction "2_2") (pintype "passive"))
      (node (ref "Q505") (pin "3") (pinfunction "C_3") (pintype "passive"))
      (node (ref "R521") (pin "1") (pinfunction "1_1") (pintype "passive"))
      (node (ref "U511") (pin "6") (pinfunction "P2_6") (pintype "passive"))
    )
    (net (code "22") (name "/SAC12") (class "Default")
      (node (ref "C513") (pin "2") (pinfunction "2_2") (pintype "passive"))
      (node (ref "Q509") (pin "3") (pinfunction "C_3") (pintype "passive"))
      (node (ref "R535") (pin "1") (pinfunction "1_1") (pintype "passive"))
      (node (ref "U511") (pin "9") (pinfunction "P4_9") (pintype "passive"))
    )
    (net (code "23") (name "/SAC13") (class "Default")
      (node (ref "C515") (pin "2") (pinfunction "2_2") (pintype "passive"))
      (node (ref "Q511") (pin "3") (pinfunction "C_3") (pintype "passive"))
      (node (ref "R543") (pin "1") (pinfunction "1_1") (pintype "passive"))
      (node (ref "U511") (pin "11") (pinfunction "P6_11") (pintype "passive"))
    )
    (net (code "24") (name "/SAC14") (class "Default")
      (node (ref "C519") (pin "2") (pinfunction "2_2") (pintype "passive"))
      (node (ref "Q513") (pin "3") (pinfunction "C_3") (pintype "passive"))
      (node (ref "R551") (pin "1") (pinfunction "1_1") (pintype "passive"))
      (node (ref "U514") (pin "4") (pinfunction "P0_4") (pintype "passive"))
    )
    (net (code "25") (name "/SAC15") (class "Default")
      (node (ref "C521") (pin "2") (pinfunction "2_2") (pintype "passive"))
      (node (ref "Q516") (pin "3") (pinfunction "C_3") (pintype "passive"))
      (node (ref "R562") (pin "1") (pinfunction "1_1") (pintype "passive"))
      (node (ref "U514") (pin "6") (pinfunction "P2_6") (pintype "passive"))
    )
    (net (code "26") (name "/SAC16") (class "Default")
      (node (ref "C523") (pin "2") (pinfunction "2_2") (pintype "passive"))
      (node (ref "Q503") (pin "3") (pinfunction "C_3") (pintype "passive"))
      (node (ref "R507") (pin "1") (pinfunction "1_1") (pintype "passive"))
      (node (ref "U514") (pin "9") (pinfunction "P4_9") (pintype "passive"))
    )
    (net (code "27") (name "/SAC17") (class "Default")
      (node (ref "C525") (pin "2") (pinfunction "2_2") (pintype "passive"))
      (node (ref "Q507") (pin "3") (pinfunction "C_3") (pintype "passive"))
      (node (ref "R523") (pin "1") (pinfunction "1_1") (pintype "passive"))
      (node (ref "U514") (pin "11") (pinfunction "P6_11") (pintype "passive"))
    )
    (net (code "28") (name "/SAC20") (class "Default")
      (node (ref "C510") (pin "2") (pinfunction "2_2") (pintype "passive"))
      (node (ref "Q502") (pin "3") (pinfunction "C_3") (pintype "passive"))
      (node (ref "R506") (pin "1") (pinfunction "1_1") (pintype "passive"))
      (node (ref "U511") (pin "5") (pinfunction "P1_5") (pintype "passive"))
    )
    (net (code "29") (name "/SAC21") (class "Default")
      (node (ref "C512") (pin "2") (pinfunction "2_2") (pintype "passive"))
      (node (ref "Q506") (pin "3") (pinfunction "C_3") (pintype "passive"))
      (node (ref "R522") (pin "1") (pinfunction "1_1") (pintype "passive"))
      (node (ref "U511") (pin "7") (pinfunction "P3_7") (pintype "passive"))
    )
    (net (code "30") (name "/SAC22") (class "Default")
      (node (ref "C514") (pin "2") (pinfunction "2_2") (pintype "passive"))
      (node (ref "Q510") (pin "3") (pinfunction "C_3") (pintype "passive"))
      (node (ref "R536") (pin "1") (pinfunction "1_1") (pintype "passive"))
      (node (ref "U511") (pin "10") (pinfunction "P5_10") (pintype "passive"))
    )
    (net (code "31") (name "/SAC23") (class "Default")
      (node (ref "C516") (pin "2") (pinfunction "2_2") (pintype "passive"))
      (node (ref "Q512") (pin "3") (pinfunction "C_3") (pintype "passive"))
      (node (ref "R544") (pin "1") (pinfunction "1_1") (pintype "passive"))
      (node (ref "U511") (pin "12") (pinfunction "P7_12") (pintype "passive"))
    )
    (net (code "32") (name "/SAC24") (class "Default")
      (node (ref "C520") (pin "2") (pinfunction "2_2") (pintype "passive"))
      (node (ref "Q514") (pin "3") (pinfunction "C_3") (pintype "passive"))
      (node (ref "R552") (pin "1") (pinfunction "1_1") (pintype "passive"))
      (node (ref "U514") (pin "5") (pinfunction "P1_5") (pintype "passive"))
    )
    (net (code "33") (name "/SAC25") (class "Default")
      (node (ref "C522") (pin "2") (pinfunction "2_2") (pintype "passive"))
      (node (ref "Q517") (pin "3") (pinfunction "C_3") (pintype "passive"))
      (node (ref "R563") (pin "1") (pinfunction "1_1") (pintype "passive"))
      (node (ref "U514") (pin "7") (pinfunction "P3_7") (pintype "passive"))
    )
    (net (code "34") (name "/SAC26") (class "Default")
      (node (ref "C524") (pin "2") (pinfunction "2_2") (pintype "passive"))
      (node (ref "Q504") (pin "3") (pinfunction "C_3") (pintype "passive"))
      (node (ref "R508") (pin "1") (pinfunction "1_1") (pintype "passive"))
      (node (ref "U514") (pin "10") (pinfunction "P5_10") (pintype "passive"))
    )
    (net (code "35") (name "/SAC27") (class "Default")
      (node (ref "C526") (pin "2") (pinfunction "2_2") (pintype "passive"))
      (node (ref "Q508") (pin "3") (pinfunction "C_3") (pintype "passive"))
      (node (ref "R524") (pin "1") (pinfunction "1_1") (pintype "passive"))
      (node (ref "U514") (pin "12") (pinfunction "P7_12") (pintype "passive"))
    )
    (net (code "36") (name "3V3_EXT") (class "Default")
      (node (ref "C527") (pin "1") (pinfunction "1_1") (pintype "passive"))
      (node (ref "C528") (pin "1") (pinfunction "1_1") (pintype "passive"))
      (node (ref "C533") (pin "1") (pinfunction "1_1") (pintype "passive"))
      (node (ref "C534") (pin "1") (pinfunction "1_1") (pintype "passive"))
      (node (ref "C556") (pin "1") (pinfunction "1_1") (pintype "passive"))
      (node (ref "C557") (pin "1") (pinfunction "1_1") (pintype "passive"))
      (node (ref "C558") (pin "1") (pinfunction "1_1") (pintype "passive"))
      (node (ref "C559") (pin "1") (pinfunction "1_1") (pintype "passive"))
      (node (ref "C560") (pin "1") (pinfunction "1_1") (pintype "passive"))
      (node (ref "R505") (pin "2") (pinfunction "2_2") (pintype "passive"))
      (node (ref "R506") (pin "2") (pinfunction "2_2") (pintype "passive"))
      (node (ref "R507") (pin "2") (pinfunction "2_2") (pintype "passive"))
      (node (ref "R508") (pin "2") (pinfunction "2_2") (pintype "passive"))
      (node (ref "R521") (pin "2") (pinfunction "2_2") (pintype "passive"))
      (node (ref "R522") (pin "2") (pinfunction "2_2") (pintype "passive"))
      (node (ref "R523") (pin "2") (pinfunction "2_2") (pintype "passive"))
      (node (ref "R524") (pin "2") (pinfunction "2_2") (pintype "passive"))
      (node (ref "R535") (pin "2") (pinfunction "2_2") (pintype "passive"))
      (node (ref "R536") (pin "2") (pinfunction "2_2") (pintype "passive"))
      (node (ref "R543") (pin "2") (pinfunction "2_2") (pintype "passive"))
      (node (ref "R544") (pin "2") (pinfunction "2_2") (pintype "passive"))
      (node (ref "R551") (pin "2") (pinfunction "2_2") (pintype "passive"))
      (node (ref "R552") (pin "2") (pinfunction "2_2") (pintype "passive"))
      (node (ref "R558") (pin "2") (pinfunction "2_2") (pintype "passive"))
      (node (ref "R562") (pin "2") (pinfunction "2_2") (pintype "passive"))
      (node (ref "R563") (pin "2") (pinfunction "2_2") (pintype "passive"))
      (node (ref "U501") (pin "4") (pinfunction "C_4") (pintype "passive"))
      (node (ref "U502") (pin "4") (pinfunction "C_4") (pintype "passive"))
      (node (ref "U503") (pin "4") (pinfunction "C_4") (pintype "passive"))
      (node (ref "U504") (pin "4") (pinfunction "C_4") (pintype "passive"))
      (node (ref "U505") (pin "4") (pinfunction "C_4") (pintype "passive"))
      (node (ref "U506") (pin "4") (pinfunction "C_4") (pintype "passive"))
      (node (ref "U507") (pin "4") (pinfunction "C_4") (pintype "passive"))
      (node (ref "U508") (pin "4") (pinfunction "C_4") (pintype "passive"))
      (node (ref "U509") (pin "4") (pinfunction "C_4") (pintype "passive"))
      (node (ref "U510") (pin "4") (pinfunction "C_4") (pintype "passive"))
      (node (ref "U511") (pin "16") (pinfunction "VDD_16") (pintype "passive"))
      (node (ref "U512") (pin "4") (pinfunction "C_4") (pintype "passive"))
      (node (ref "U513") (pin "4") (pinfunction "C_4") (pintype "passive"))
      (node (ref "U514") (pin "16") (pinfunction "VDD_16") (pintype "passive"))
      (node (ref "U514") (pin "3") (pinfunction "A2_3") (pintype "passive"))
      (node (ref "U515") (pin "4") (pinfunction "C_4") (pintype "passive"))
      (node (ref "U516") (pin "4") (pinfunction "C_4") (pintype "passive"))
      (node (ref "U517") (pin "4") (pinfunction "C_4") (pintype "passive"))
      (node (ref "U518") (pin "4") (pinfunction "C_4") (pintype "passive"))
      (node (ref "U519") (pin "4") (pinfunction "C_4") (pintype "passive"))
    )
    (net (code "37") (name "ACL") (class "Default")
      (node (ref "R557") (pin "1") (pinfunction "1_1") (pintype "passive"))
    )
    (net (code "38") (name "ACN") (class "Default")
      (node (ref "R509") (pin "1") (pinfunction "1_1") (pintype "passive"))
      (node (ref "R510") (pin "1") (pinfunction "1_1") (pintype "passive"))
      (node (ref "R511") (pin "1") (pinfunction "1_1") (pintype "passive"))
      (node (ref "R512") (pin "1") (pinfunction "1_1") (pintype "passive"))
      (node (ref "R525") (pin "1") (pinfunction "1_1") (pintype "passive"))
      (node (ref "R526") (pin "1") (pinfunction "1_1") (pintype "passive"))
      (node (ref "R527") (pin "1") (pinfunction "1_1") (pintype "passive"))
      (node (ref "R528") (pin "1") (pinfunction "1_1") (pintype "passive"))
      (node (ref "R537") (pin "1") (pinfunction "1_1") (pintype "passive"))
      (node (ref "R538") (pin "1") (pinfunction "1_1") (pintype "passive"))
      (node (ref "R545") (pin "1") (pinfunction "1_1") (pintype "passive"))
      (node (ref "R546") (pin "1") (pinfunction "1_1") (pintype "passive"))
      (node (ref "R553") (pin "1") (pinfunction "1_1") (pintype "passive"))
      (node (ref "R554") (pin "1") (pinfunction "1_1") (pintype "passive"))
      (node (ref "R559") (pin "1") (pinfunction "1_1") (pintype "passive"))
      (node (ref "R564") (pin "1") (pinfunction "1_1") (pintype "passive"))
      (node (ref "R565") (pin "1") (pinfunction "1_1") (pintype "passive"))
    )
    (net (code "39") (name "GND") (class "Default")
      (node (ref "C501") (pin "2") (pinfunction "2_2") (pintype "passive"))
      (node (ref "C502") (pin "2") (pinfunction "2_2") (pintype "passive"))
      (node (ref "C503") (pin "2") (pinfunction "2_2") (pintype "passive"))
      (node (ref "C504") (pin "2") (pinfunction "2_2") (pintype "passive"))
      (node (ref "C505") (pin "2") (pinfunction "2_2") (pintype "passive"))
      (node (ref "C506") (pin "2") (pinfunction "2_2") (pintype "passive"))
      (node (ref "C507") (pin "2") (pinfunction "2_2") (pintype "passive"))
      (node (ref "C508") (pin "2") (pinfunction "2_2") (pintype "passive"))
      (node (ref "C509") (pin "1") (pinfunction "1_1") (pintype "passive"))
      (node (ref "C510") (pin "1") (pinfunction "1_1") (pintype "passive"))
      (node (ref "C511") (pin "1") (pinfunction "1_1") (pintype "passive"))
      (node (ref "C512") (pin "1") (pinfunction "1_1") (pintype "passive"))
      (node (ref "C513") (pin "1") (pinfunction "1_1") (pintype "passive"))
      (node (ref "C514") (pin "1") (pinfunction "1_1") (pintype "passive"))
      (node (ref "C515") (pin "1") (pinfunction "1_1") (pintype "passive"))
      (node (ref "C516") (pin "1") (pinfunction "1_1") (pintype "passive"))
      (node (ref "C517") (pin "2") (pinfunction "2_2") (pintype "passive"))
      (node (ref "C518") (pin "2") (pinfunction "2_2") (pintype "passive"))
      (node (ref "C519") (pin "1") (pinfunction "1_1") (pintype "passive"))
      (node (ref "C520") (pin "1") (pinfunction "1_1") (pintype "passive"))
      (node (ref "C521") (pin "1") (pinfunction "1_1") (pintype "passive"))
      (node (ref "C522") (pin "1") (pinfunction "1_1") (pintype "passive"))
      (node (ref "C523") (pin "1") (pinfunction "1_1") (pintype "passive"))
      (node (ref "C524") (pin "1") (pinfunction "1_1") (pintype "passive"))
      (node (ref "C525") (pin "1") (pinfunction "1_1") (pintype "passive"))
      (node (ref "C526") (pin "1") (pinfunction "1_1") (pintype "passive"))
      (node (ref "C527") (pin "2") (pinfunction "2_2") (pintype "passive"))
      (node (ref "C528") (pin "2") (pinfunction "2_2") (pintype "passive"))
      (node (ref "C529") (pin "2") (pinfunction "2_2") (pintype "passive"))
      (node (ref "C530") (pin "2") (pinfunction "2_2") (pintype "passive"))
      (node (ref "C531") (pin "2") (pinfunction "2_2") (pintype "passive"))
      (node (ref "C532") (pin "2") (pinfunction "2_2") (pintype "passive"))
      (node (ref "C533") (pin "2") (pinfunction "2_2") (pintype "passive"))
      (node (ref "C534") (pin "2") (pinfunction "2_2") (pintype "passive"))
      (node (ref "C535") (pin "2") (pinfunction "2_2") (pintype "passive"))
      (node (ref "C536") (pin "2") (pinfunction "2_2") (pintype "passive"))
      (node (ref "C537") (pin "2") (pinfunction "2_2") (pintype "passive"))
      (node (ref "C538") (pin "1") (pinfunction "1_1") (pintype "passive"))
      (node (ref "C539") (pin "2") (pinfunction "2_2") (pintype "passive"))
      (node (ref "C540") (pin "2") (pinfunction "2_2") (pintype "passive"))
      (node (ref "C541") (pin "2") (pinfunction "2_2") (pintype "passive"))
      (node (ref "C542") (pin "2") (pinfunction "2_2") (pintype "passive"))
      (node (ref "C543") (pin "2") (pinfunction "2_2") (pintype "passive"))
      (node (ref "C544") (pin "2") (pinfunction "2_2") (pintype "passive"))
      (node (ref "C545") (pin "2") (pinfunction "2_2") (pintype "passive"))
      (node (ref "C546") (pin "2") (pinfunction "2_2") (pintype "passive"))
      (node (ref "C547") (pin "2") (pinfunction "2_2") (pintype "passive"))
      (node (ref "C548") (pin "2") (pinfunction "2_2") (pintype "passive"))
      (node (ref "C549") (pin "2") (pinfunction "2_2") (pintype "passive"))
      (node (ref "C550") (pin "2") (pinfunction "2_2") (pintype "passive"))
      (node (ref "C551") (pin "2") (pinfunction "2_2") (pintype "passive"))
      (node (ref "C552") (pin "2") (pinfunction "2_2") (pintype "passive"))
      (node (ref "C553") (pin "2") (pinfunction "2_2") (pintype "passive"))
      (node (ref "C554") (pin "2") (pinfunction "2_2") (pintype "passive"))
      (node (ref "C555") (pin "2") (pinfunction "2_2") (pintype "passive"))
      (node (ref "C556") (pin "2") (pinfunction "2_2") (pintype "passive"))
      (node (ref "C557") (pin "2") (pinfunction "2_2") (pintype "passive"))
      (node (ref "C558") (pin "2") (pinfunction "2_2") (pintype "passive"))
      (node (ref "C559") (pin "2") (pinfunction "2_2") (pintype "passive"))
      (node (ref "C560") (pin "2") (pinfunction "2_2") (pintype "passive"))
      (node (ref "Q501") (pin "2") (pinfunction "E_2") (pintype "passive"))
      (node (ref "Q502") (pin "2") (pinfunction "E_2") (pintype "passive"))
      (node (ref "Q503") (pin "2") (pinfunction "E_2") (pintype "passive"))
      (node (ref "Q504") (pin "2") (pinfunction "E_2") (pintype "passive"))
      (node (ref "Q505") (pin "2") (pinfunction "E_2") (pintype "passive"))
      (node (ref "Q506") (pin "2") (pinfunction "E_2") (pintype "passive"))
      (node (ref "Q507") (pin "2") (pinfunction "E_2") (pintype "passive"))
      (node (ref "Q508") (pin "2") (pinfunction "E_2") (pintype "passive"))
      (node (ref "Q509") (pin "2") (pinfunction "E_2") (pintype "passive"))
      (node (ref "Q510") (pin "2") (pinfunction "E_2") (pintype "passive"))
      (node (ref "Q511") (pin "2") (pinfunction "E_2") (pintype "passive"))
      (node (ref "Q512") (pin "2") (pinfunction "E_2") (pintype "passive"))
      (node (ref "Q513") (pin "2") (pinfunction "E_2") (pintype "passive"))
      (node (ref "Q514") (pin "2") (pinfunction "E_2") (pintype "passive"))
      (node (ref "Q515") (pin "2") (pinfunction "E_2") (pintype "passive"))
      (node (ref "Q516") (pin "2") (pinfunction "E_2") (pintype "passive"))
      (node (ref "Q517") (pin "2") (pinfunction "E_2") (pintype "passive"))
      (node (ref "R513") (pin "1") (pinfunction "1_1") (pintype "passive"))
      (node (ref "R514") (pin "1") (pinfunction "1_1") (pintype "passive"))
      (node (ref "R515") (pin "1") (pinfunction "1_1") (pintype "passive"))
      (node (ref "R516") (pin "1") (pinfunction "1_1") (pintype "passive"))
      (node (ref "R529") (pin "1") (pinfunction "1_1") (pintype "passive"))
      (node (ref "R530") (pin "1") (pinfunction "1_1") (pintype "passive"))
      (node (ref "R531") (pin "1") (pinfunction "1_1") (pintype "passive"))
      (node (ref "R532") (pin "1") (pinfunction "1_1") (pintype "passive"))
      (node (ref "R539") (pin "1") (pinfunction "1_1") (pintype "passive"))
      (node (ref "R540") (pin "1") (pinfunction "1_1") (pintype "passive"))
      (node (ref "R547") (pin "1") (pinfunction "1_1") (pintype "passive"))
      (node (ref "R548") (pin "1") (pinfunction "1_1") (pintype "passive"))
      (node (ref "R555") (pin "1") (pinfunction "1_1") (pintype "passive"))
      (node (ref "R556") (pin "1") (pinfunction "1_1") (pintype "passive"))
      (node (ref "R566") (pin "1") (pinfunction "1_1") (pintype "passive"))
      (node (ref "R567") (pin "1") (pinfunction "1_1") (pintype "passive"))
      (node (ref "R568") (pin "1") (pinfunction "1_1") (pintype "passive"))
      (node (ref "U511") (pin "1") (pinfunction "A0_1") (pintype "passive"))
      (node (ref "U511") (pin "2") (pinfunction "A1_2") (pintype "passive"))
      (node (ref "U511") (pin "3") (pinfunction "A2_3") (pintype "passive"))
      (node (ref "U511") (pin "8") (pinfunction "VSS_8") (pintype "passive"))
      (node (ref "U514") (pin "1") (pinfunction "A0_1") (pintype "passive"))
      (node (ref "U514") (pin "2") (pinfunction "A1_2") (pintype "passive"))
      (node (ref "U514") (pin "8") (pinfunction "VSS_8") (pintype "passive"))
    )
    (net (code "40") (name "Net-(Q501-B)") (class "Default")
      (node (ref "Q501") (pin "1") (pinfunction "B_1") (pintype "passive"))
      (node (ref "R569") (pin "1") (pinfunction "1_1") (pintype "passive"))
    )
    (net (code "41") (name "Net-(Q502-B)") (class "Default")
      (node (ref "Q502") (pin "1") (pinfunction "B_1") (pintype "passive"))
      (node (ref "R570") (pin "1") (pinfunction "1_1") (pintype "passive"))
    )
    (net (code "42") (name "Net-(Q503-B)") (class "Default")
      (node (ref "Q503") (pin "1") (pinfunction "B_1") (pintype "passive"))
      (node (ref "R571") (pin "1") (pinfunction "1_1") (pintype "passive"))
    )
    (net (code "43") (name "Net-(Q504-B)") (class "Default")
      (node (ref "Q504") (pin "1") (pinfunction "B_1") (pintype "passive"))
      (node (ref "R572") (pin "1") (pinfunction "1_1") (pintype "passive"))
    )
    (net (code "44") (name "Net-(Q505-B)") (class "Default")
      (node (ref "Q505") (pin "1") (pinfunction "B_1") (pintype "passive"))
      (node (ref "R573") (pin "1") (pinfunction "1_1") (pintype "passive"))
    )
    (net (code "45") (name "Net-(Q506-B)") (class "Default")
      (node (ref "Q506") (pin "1") (pinfunction "B_1") (pintype "passive"))
      (node (ref "R574") (pin "1") (pinfunction "1_1") (pintype "passive"))
    )
    (net (code "46") (name "Net-(Q507-B)") (class "Default")
      (node (ref "Q507") (pin "1") (pinfunction "B_1") (pintype "passive"))
      (node (ref "R575") (pin "1") (pinfunction "1_1") (pintype "passive"))
    )
    (net (code "47") (name "Net-(Q508-B)") (class "Default")
      (node (ref "Q508") (pin "1") (pinfunction "B_1") (pintype "passive"))
      (node (ref "R576") (pin "1") (pinfunction "1_1") (pintype "passive"))
    )
    (net (code "48") (name "Net-(Q509-B)") (class "Default")
      (node (ref "Q509") (pin "1") (pinfunction "B_1") (pintype "passive"))
      (node (ref "R577") (pin "1") (pinfunction "1_1") (pintype "passive"))
    )
    (net (code "49") (name "Net-(Q510-B)") (class "Default")
      (node (ref "Q510") (pin "1") (pinfunction "B_1") (pintype "passive"))
      (node (ref "R578") (pin "1") (pinfunction "1_1") (pintype "passive"))
    )
    (net (code "50") (name "Net-(Q511-B)") (class "Default")
      (node (ref "Q511") (pin "1") (pinfunction "B_1") (pintype "passive"))
      (node (ref "R579") (pin "1") (pinfunction "1_1") (pintype "passive"))
    )
    (net (code "51") (name "Net-(Q512-B)") (class "Default")
      (node (ref "Q512") (pin "1") (pinfunction "B_1") (pintype "passive"))
      (node (ref "R580") (pin "1") (pinfunction "1_1") (pintype "passive"))
    )
    (net (code "52") (name "Net-(Q513-B)") (class "Default")
      (node (ref "Q513") (pin "1") (pinfunction "B_1") (pintype "passive"))
      (node (ref "R581") (pin "1") (pinfunction "1_1") (pintype "passive"))
    )
    (net (code "53") (name "Net-(Q514-B)") (class "Default")
      (node (ref "Q514") (pin "1") (pinfunction "B_1") (pintype "passive"))
      (node (ref "R582") (pin "1") (pinfunction "1_1") (pintype "passive"))
    )
    (net (code "54") (name "Net-(Q515-B)") (class "Default")
      (node (ref "Q515") (pin "1") (pinfunction "B_1") (pintype "passive"))
      (node (ref "R583") (pin "1") (pinfunction "1_1") (pintype "passive"))
    )
    (net (code "55") (name "Net-(Q516-B)") (class "Default")
      (node (ref "Q516") (pin "1") (pinfunction "B_1") (pintype "passive"))
      (node (ref "R584") (pin "1") (pinfunction "1_1") (pintype "passive"))
    )
    (net (code "56") (name "Net-(Q517-B)") (class "Default")
      (node (ref "Q517") (pin "1") (pinfunction "B_1") (pintype "passive"))
      (node (ref "R585") (pin "1") (pinfunction "1_1") (pintype "passive"))
    )
    (net (code "57") (name "Net-(U501-A{slash}C)") (class "Default")
      (node (ref "R501") (pin "2") (pinfunction "2_2") (pintype "passive"))
      (node (ref "U501") (pin "1") (pinfunction "A/C_1") (pintype "passive"))
    )
    (net (code "58") (name "Net-(U501-C{slash}A)") (class "Default")
      (node (ref "R509") (pin "2") (pinfunction "2_2") (pintype "passive"))
      (node (ref "U501") (pin "2") (pinfunction "C/A_2") (pintype "passive"))
    )
    (net (code "59") (name "Net-(U501-E)") (class "Default")
      (node (ref "C501") (pin "1") (pinfunction "1_1") (pintype "passive"))
      (node (ref "C539") (pin "1") (pinfunction "1_1") (pintype "passive"))
      (node (ref "R513") (pin "2") (pinfunction "2_2") (pintype "passive"))
      (node (ref "R569") (pin "2") (pinfunction "2_2") (pintype "passive"))
      (node (ref "U501") (pin "3") (pinfunction "E_3") (pintype "passive"))
    )
    (net (code "60") (name "Net-(U502-A{slash}C)") (class "Default")
      (node (ref "R502") (pin "2") (pinfunction "2_2") (pintype "passive"))
      (node (ref "U502") (pin "1") (pinfunction "A/C_1") (pintype "passive"))
    )
    (net (code "61") (name "Net-(U502-C{slash}A)") (class "Default")
      (node (ref "R510") (pin "2") (pinfunction "2_2") (pintype "passive"))
      (node (ref "U502") (pin "2") (pinfunction "C/A_2") (pintype "passive"))
    )
    (net (code "62") (name "Net-(U502-E)") (class "Default")
      (node (ref "C502") (pin "1") (pinfunction "1_1") (pintype "passive"))
      (node (ref "C540") (pin "1") (pinfunction "1_1") (pintype "passive"))
      (node (ref "R514") (pin "2") (pinfunction "2_2") (pintype "passive"))
      (node (ref "R570") (pin "2") (pinfunction "2_2") (pintype "passive"))
      (node (ref "U502") (pin "3") (pinfunction "E_3") (pintype "passive"))
    )
    (net (code "63") (name "Net-(U503-A{slash}C)") (class "Default")
      (node (ref "R503") (pin "2") (pinfunction "2_2") (pintype "passive"))
      (node (ref "U503") (pin "1") (pinfunction "A/C_1") (pintype "passive"))
    )
    (net (code "64") (name "Net-(U503-C{slash}A)") (class "Default")
      (node (ref "R511") (pin "2") (pinfunction "2_2") (pintype "passive"))
      (node (ref "U503") (pin "2") (pinfunction "C/A_2") (pintype "passive"))
    )
    (net (code "65") (name "Net-(U503-E)") (class "Default")
      (node (ref "C503") (pin "1") (pinfunction "1_1") (pintype "passive"))
      (node (ref "C541") (pin "1") (pinfunction "1_1") (pintype "passive"))
      (node (ref "R515") (pin "2") (pinfunction "2_2") (pintype "passive"))
      (node (ref "R571") (pin "2") (pinfunction "2_2") (pintype "passive"))
      (node (ref "U503") (pin "3") (pinfunction "E_3") (pintype "passive"))
    )
    (net (code "66") (name "Net-(U504-A{slash}C)") (class "Default")
      (node (ref "R504") (pin "2") (pinfunction "2_2") (pintype "passive"))
      (node (ref "U504") (pin "1") (pinfunction "A/C_1") (pintype "passive"))
    )
    (net (code "67") (name "Net-(U504-C{slash}A)") (class "Default")
      (node (ref "R512") (pin "2") (pinfunction "2_2") (pintype "passive"))
      (node (ref "U504") (pin "2") (pinfunction "C/A_2") (pintype "passive"))
    )
    (net (code "68") (name "Net-(U504-E)") (class "Default")
      (node (ref "C504") (pin "1") (pinfunction "1_1") (pintype "passive"))
      (node (ref "C542") (pin "1") (pinfunction "1_1") (pintype "passive"))
      (node (ref "R516") (pin "2") (pinfunction "2_2") (pintype "passive"))
      (node (ref "R572") (pin "2") (pinfunction "2_2") (pintype "passive"))
      (node (ref "U504") (pin "3") (pinfunction "E_3") (pintype "passive"))
    )
    (net (code "69") (name "Net-(U505-A{slash}C)") (class "Default")
      (node (ref "R517") (pin "2") (pinfunction "2_2") (pintype "passive"))
      (node (ref "U505") (pin "1") (pinfunction "A/C_1") (pintype "passive"))
    )
    (net (code "70") (name "Net-(U505-C{slash}A)") (class "Default")
      (node (ref "R525") (pin "2") (pinfunction "2_2") (pintype "passive"))
      (node (ref "U505") (pin "2") (pinfunction "C/A_2") (pintype "passive"))
    )
    (net (code "71") (name "Net-(U505-E)") (class "Default")
      (node (ref "C505") (pin "1") (pinfunction "1_1") (pintype "passive"))
      (node (ref "C543") (pin "1") (pinfunction "1_1") (pintype "passive"))
      (node (ref "R529") (pin "2") (pinfunction "2_2") (pintype "passive"))
      (node (ref "R573") (pin "2") (pinfunction "2_2") (pintype "passive"))
      (node (ref "U505") (pin "3") (pinfunction "E_3") (pintype "passive"))
    )
    (net (code "72") (name "Net-(U506-A{slash}C)") (class "Default")
      (node (ref "R518") (pin "2") (pinfunction "2_2") (pintype "passive"))
      (node (ref "U506") (pin "1") (pinfunction "A/C_1") (pintype "passive"))
    )
    (net (code "73") (name "Net-(U506-C{slash}A)") (class "Default")
      (node (ref "R526") (pin "2") (pinfunction "2_2") (pintype "passive"))
      (node (ref "U506") (pin "2") (pinfunction "C/A_2") (pintype "passive"))
    )
    (net (code "74") (name "Net-(U506-E)") (class "Default")
      (node (ref "C506") (pin "1") (pinfunction "1_1") (pintype "passive"))
      (node (ref "C544") (pin "1") (pinfunction "1_1") (pintype "passive"))
      (node (ref "R530") (pin "2") (pinfunction "2_2") (pintype "passive"))
      (node (ref "R574") (pin "2") (pinfunction "2_2") (pintype "passive"))
      (node (ref "U506") (pin "3") (pinfunction "E_3") (pintype "passive"))
    )
    (net (code "75") (name "Net-(U507-A{slash}C)") (class "Default")
      (node (ref "R519") (pin "2") (pinfunction "2_2") (pintype "passive"))
      (node (ref "U507") (pin "1") (pinfunction "A/C_1") (pintype "passive"))
    )
    (net (code "76") (name "Net-(U507-C{slash}A)") (class "Default")
      (node (ref "R527") (pin "2") (pinfunction "2_2") (pintype "passive"))
      (node (ref "U507") (pin "2") (pinfunction "C/A_2") (pintype "passive"))
    )
    (net (code "77") (name "Net-(U507-E)") (class "Default")
      (node (ref "C507") (pin "1") (pinfunction "1_1") (pintype "passive"))
      (node (ref "C545") (pin "1") (pinfunction "1_1") (pintype "passive"))
      (node (ref "R531") (pin "2") (pinfunction "2_2") (pintype "passive"))
      (node (ref "R575") (pin "2") (pinfunction "2_2") (pintype "passive"))
      (node (ref "U507") (pin "3") (pinfunction "E_3") (pintype "passive"))
    )
    (net (code "78") (name "Net-(U508-A{slash}C)") (class "Default")
      (node (ref "R520") (pin "2") (pinfunction "2_2") (pintype "passive"))
      (node (ref "U508") (pin "1") (pinfunction "A/C_1") (pintype "passive"))
    )
    (net (code "79") (name "Net-(U508-C{slash}A)") (class "Default")
      (node (ref "R528") (pin "2") (pinfunction "2_2") (pintype "passive"))
      (node (ref "U508") (pin "2") (pinfunction "C/A_2") (pintype "passive"))
    )
    (net (code "80") (name "Net-(U508-E)") (class "Default")
      (node (ref "C508") (pin "1") (pinfunction "1_1") (pintype "passive"))
      (node (ref "C546") (pin "1") (pinfunction "1_1") (pintype "passive"))
      (node (ref "R532") (pin "2") (pinfunction "2_2") (pintype "passive"))
      (node (ref "R576") (pin "2") (pinfunction "2_2") (pintype "passive"))
      (node (ref "U508") (pin "3") (pinfunction "E_3") (pintype "passive"))
    )
    (net (code "81") (name "Net-(U509-A{slash}C)") (class "Default")
      (node (ref "R533") (pin "2") (pinfunction "2_2") (pintype "passive"))
      (node (ref "U509") (pin "1") (pinfunction "A/C_1") (pintype "passive"))
    )
    (net (code "82") (name "Net-(U509-C{slash}A)") (class "Default")
      (node (ref "R537") (pin "2") (pinfunction "2_2") (pintype "passive"))
      (node (ref "U509") (pin "2") (pinfunction "C/A_2") (pintype "passive"))
    )
    (net (code "83") (name "Net-(U509-E)") (class "Default")
      (node (ref "C517") (pin "1") (pinfunction "1_1") (pintype "passive"))
      (node (ref "C547") (pin "1") (pinfunction "1_1") (pintype "passive"))
      (node (ref "R539") (pin "2") (pinfunction "2_2") (pintype "passive"))
      (node (ref "R577") (pin "2") (pinfunction "2_2") (pintype "passive"))
      (node (ref "U509") (pin "3") (pinfunction "E_3") (pintype "passive"))
    )
    (net (code "84") (name "Net-(U510-A{slash}C)") (class "Default")
      (node (ref "R534") (pin "2") (pinfunction "2_2") (pintype "passive"))
      (node (ref "U510") (pin "1") (pinfunction "A/C_1") (pintype "passive"))
    )
    (net (code "85") (name "Net-(U510-C{slash}A)") (class "Default")
      (node (ref "R538") (pin "2") (pinfunction "2_2") (pintype "passive"))
      (node (ref "U510") (pin "2") (pinfunction "C/A_2") (pintype "passive"))
    )
    (net (code "86") (name "Net-(U510-E)") (class "Default")
      (node (ref "C518") (pin "1") (pinfunction "1_1") (pintype "passive"))
      (node (ref "C548") (pin "1") (pinfunction "1_1") (pintype "passive"))
      (node (ref "R540") (pin "2") (pinfunction "2_2") (pintype "passive"))
      (node (ref "R578") (pin "2") (pinfunction "2_2") (pintype "passive"))
      (node (ref "U510") (pin "3") (pinfunction "E_3") (pintype "passive"))
    )
    (net (code "87") (name "Net-(U512-A{slash}C)") (class "Default")
      (node (ref "R541") (pin "2") (pinfunction "2_2") (pintype "passive"))
      (node (ref "U512") (pin "1") (pinfunction "A/C_1") (pintype "passive"))
    )
    (net (code "88") (name "Net-(U512-C{slash}A)") (class "Default")
      (node (ref "R545") (pin "2") (pinfunction "2_2") (pintype "passive"))
      (node (ref "U512") (pin "2") (pinfunction "C/A_2") (pintype "passive"))
    )
    (net (code "89") (name "Net-(U512-E)") (class "Default")
      (node (ref "C529") (pin "1") (pinfunction "1_1") (pintype "passive"))
      (node (ref "C549") (pin "1") (pinfunction "1_1") (pintype "passive"))
      (node (ref "R547") (pin "2") (pinfunction "2_2") (pintype "passive"))
      (node (ref "R579") (pin "2") (pinfunction "2_2") (pintype "passive"))
      (node (ref "U512") (pin "3") (pinfunction "E_3") (pintype "passive"))
    )
    (net (code "90") (name "Net-(U513-A{slash}C)") (class "Default")
      (node (ref "R542") (pin "2") (pinfunction "2_2") (pintype "passive"))
      (node (ref "U513") (pin "1") (pinfunction "A/C_1") (pintype "passive"))
    )
    (net (code "91") (name "Net-(U513-C{slash}A)") (class "Default")
      (node (ref "R546") (pin "2") (pinfunction "2_2") (pintype "passive"))
      (node (ref "U513") (pin "2") (pinfunction "C/A_2") (pintype "passive"))
    )
    (net (code "92") (name "Net-(U513-E)") (class "Default")
      (node (ref "C530") (pin "1") (pinfunction "1_1") (pintype "passive"))
      (node (ref "C550") (pin "1") (pinfunction "1_1") (pintype "passive"))
      (node (ref "R548") (pin "2") (pinfunction "2_2") (pintype "passive"))
      (node (ref "R580") (pin "2") (pinfunction "2_2") (pintype "passive"))
      (node (ref "U513") (pin "3") (pinfunction "E_3") (pintype "passive"))
    )
    (net (code "93") (name "Net-(U515-A{slash}C)") (class "Default")
      (node (ref "R549") (pin "2") (pinfunction "2_2") (pintype "passive"))
      (node (ref "U515") (pin "1") (pinfunction "A/C_1") (pintype "passive"))
    )
    (net (code "94") (name "Net-(U515-C{slash}A)") (class "Default")
      (node (ref "R553") (pin "2") (pinfunction "2_2") (pintype "passive"))
      (node (ref "U515") (pin "2") (pinfunction "C/A_2") (pintype "passive"))
    )
    (net (code "95") (name "Net-(U515-E)") (class "Default")
      (node (ref "C531") (pin "1") (pinfunction "1_1") (pintype "passive"))
      (node (ref "C551") (pin "1") (pinfunction "1_1") (pintype "passive"))
      (node (ref "R555") (pin "2") (pinfunction "2_2") (pintype "passive"))
      (node (ref "R581") (pin "2") (pinfunction "2_2") (pintype "passive"))
      (node (ref "U515") (pin "3") (pinfunction "E_3") (pintype "passive"))
    )
    (net (code "96") (name "Net-(U516-A{slash}C)") (class "Default")
      (node (ref "R550") (pin "2") (pinfunction "2_2") (pintype "passive"))
      (node (ref "U516") (pin "1") (pinfunction "A/C_1") (pintype "passive"))
    )
    (net (code "97") (name "Net-(U516-C{slash}A)") (class "Default")
      (node (ref "R554") (pin "2") (pinfunction "2_2") (pintype "passive"))
      (node (ref "U516") (pin "2") (pinfunction "C/A_2") (pintype "passive"))
    )
    (net (code "98") (name "Net-(U516-E)") (class "Default")
      (node (ref "C532") (pin "1") (pinfunction "1_1") (pintype "passive"))
      (node (ref "C552") (pin "1") (pinfunction "1_1") (pintype "passive"))
      (node (ref "R556") (pin "2") (pinfunction "2_2") (pintype "passive"))
      (node (ref "R582") (pin "2") (pinfunction "2_2") (pintype "passive"))
      (node (ref "U516") (pin "3") (pinfunction "E_3") (pintype "passive"))
    )
    (net (code "99") (name "Net-(U517-A{slash}C)") (class "Default")
      (node (ref "R557") (pin "2") (pinfunction "2_2") (pintype "passive"))
      (node (ref "U517") (pin "1") (pinfunction "A/C_1") (pintype "passive"))
    )
    (net (code "100") (name "Net-(U517-C{slash}A)") (class "Default")
      (node (ref "R559") (pin "2") (pinfunction "2_2") (pintype "passive"))
      (node (ref "U517") (pin "2") (pinfunction "C/A_2") (pintype "passive"))
    )
    (net (code "101") (name "Net-(U517-E)") (class "Default")
      (node (ref "C535") (pin "1") (pinfunction "1_1") (pintype "passive"))
      (node (ref "C555") (pin "1") (pinfunction "1_1") (pintype "passive"))
      (node (ref "R566") (pin "2") (pinfunction "2_2") (pintype "passive"))
      (node (ref "R583") (pin "2") (pinfunction "2_2") (pintype "passive"))
      (node (ref "U517") (pin "3") (pinfunction "E_3") (pintype "passive"))
    )
    (net (code "102") (name "Net-(U518-A{slash}C)") (class "Default")
      (node (ref "R560") (pin "2") (pinfunction "2_2") (pintype "passive"))
      (node (ref "U518") (pin "1") (pinfunction "A/C_1") (pintype "passive"))
    )
    (net (code "103") (name "Net-(U518-C{slash}A)") (class "Default")
      (node (ref "R564") (pin "2") (pinfunction "2_2") (pintype "passive"))
      (node (ref "U518") (pin "2") (pinfunction "C/A_2") (pintype "passive"))
    )
    (net (code "104") (name "Net-(U518-E)") (class "Default")
      (node (ref "C536") (pin "1") (pinfunction "1_1") (pintype "passive"))
      (node (ref "C553") (pin "1") (pinfunction "1_1") (pintype "passive"))
      (node (ref "R567") (pin "2") (pinfunction "2_2") (pintype "passive"))
      (node (ref "R584") (pin "2") (pinfunction "2_2") (pintype "passive"))
      (node (ref "U518") (pin "3") (pinfunction "E_3") (pintype "passive"))
    )
    (net (code "105") (name "Net-(U519-A{slash}C)") (class "Default")
      (node (ref "R561") (pin "2") (pinfunction "2_2") (pintype "passive"))
      (node (ref "U519") (pin "1") (pinfunction "A/C_1") (pintype "passive"))
    )
    (net (code "106") (name "Net-(U519-C{slash}A)") (class "Default")
      (node (ref "R565") (pin "2") (pinfunction "2_2") (pintype "passive"))
      (node (ref "U519") (pin "2") (pinfunction "C/A_2") (pintype "passive"))
    )
    (net (code "107") (name "Net-(U519-E)") (class "Default")
      (node (ref "C537") (pin "1") (pinfunction "1_1") (pintype "passive"))
      (node (ref "C554") (pin "1") (pinfunction "1_1") (pintype "passive"))
      (node (ref "R568") (pin "2") (pinfunction "2_2") (pintype "passive"))
      (node (ref "R585") (pin "2") (pinfunction "2_2") (pintype "passive"))
      (node (ref "U519") (pin "3") (pinfunction "E_3") (pintype "passive"))
    )
    (net (code "108") (name "unconnected-(U511-INT-Pad13)") (class "Default")
      (node (ref "U511") (pin "13") (pinfunction "INT_13") (pintype "passive+no_connect"))
    )
    (net (code "109") (name "unconnected-(U514-INT-Pad13)") (class "Default")
      (node (ref "U514") (pin "13") (pinfunction "INT_13") (pintype "passive+no_connect"))
    )
  )
)
